# picsil_Carrier.net
KiCad netlist of a schematic drawn in EAGLE
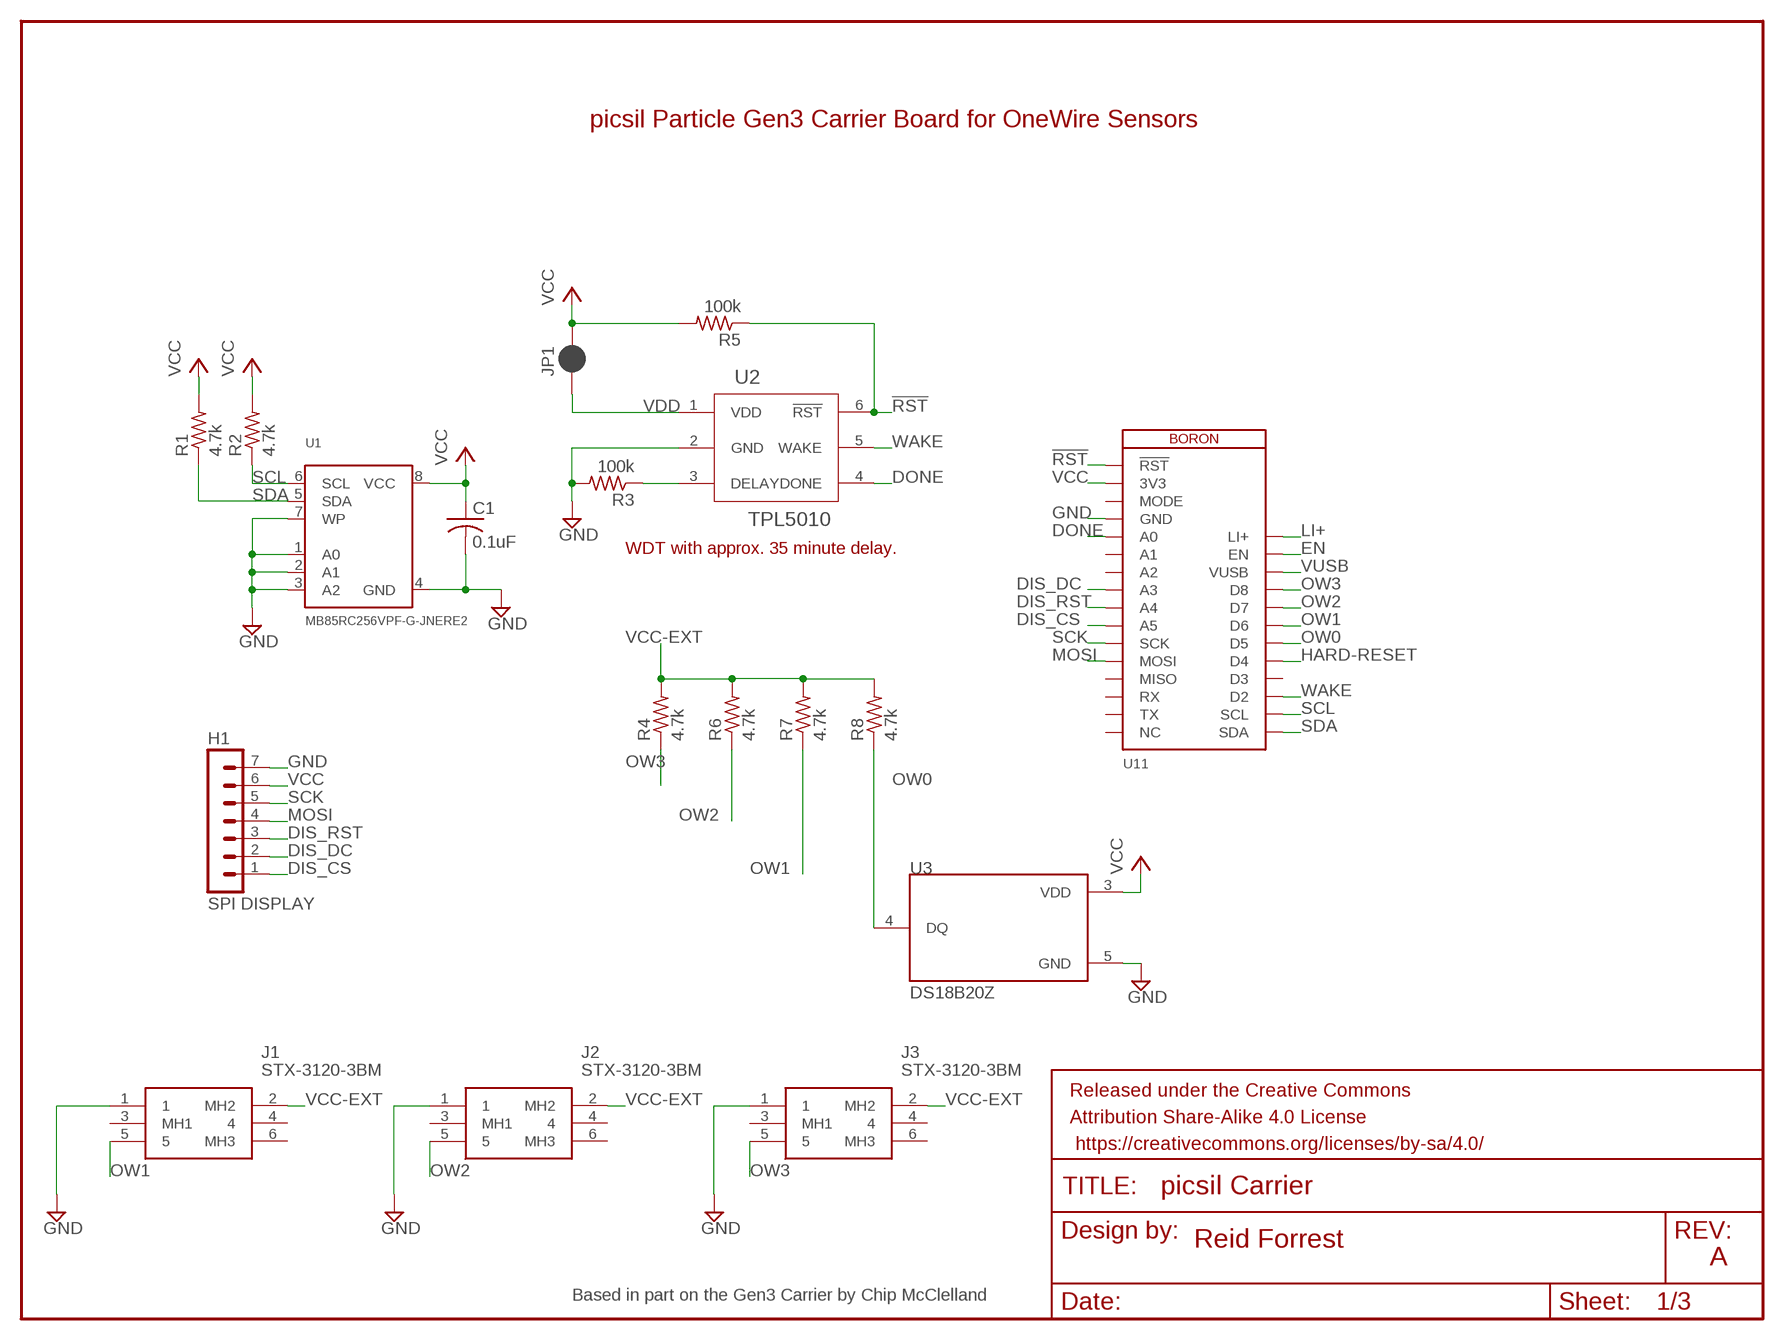
[diagram p0: schematic, sheet 1]
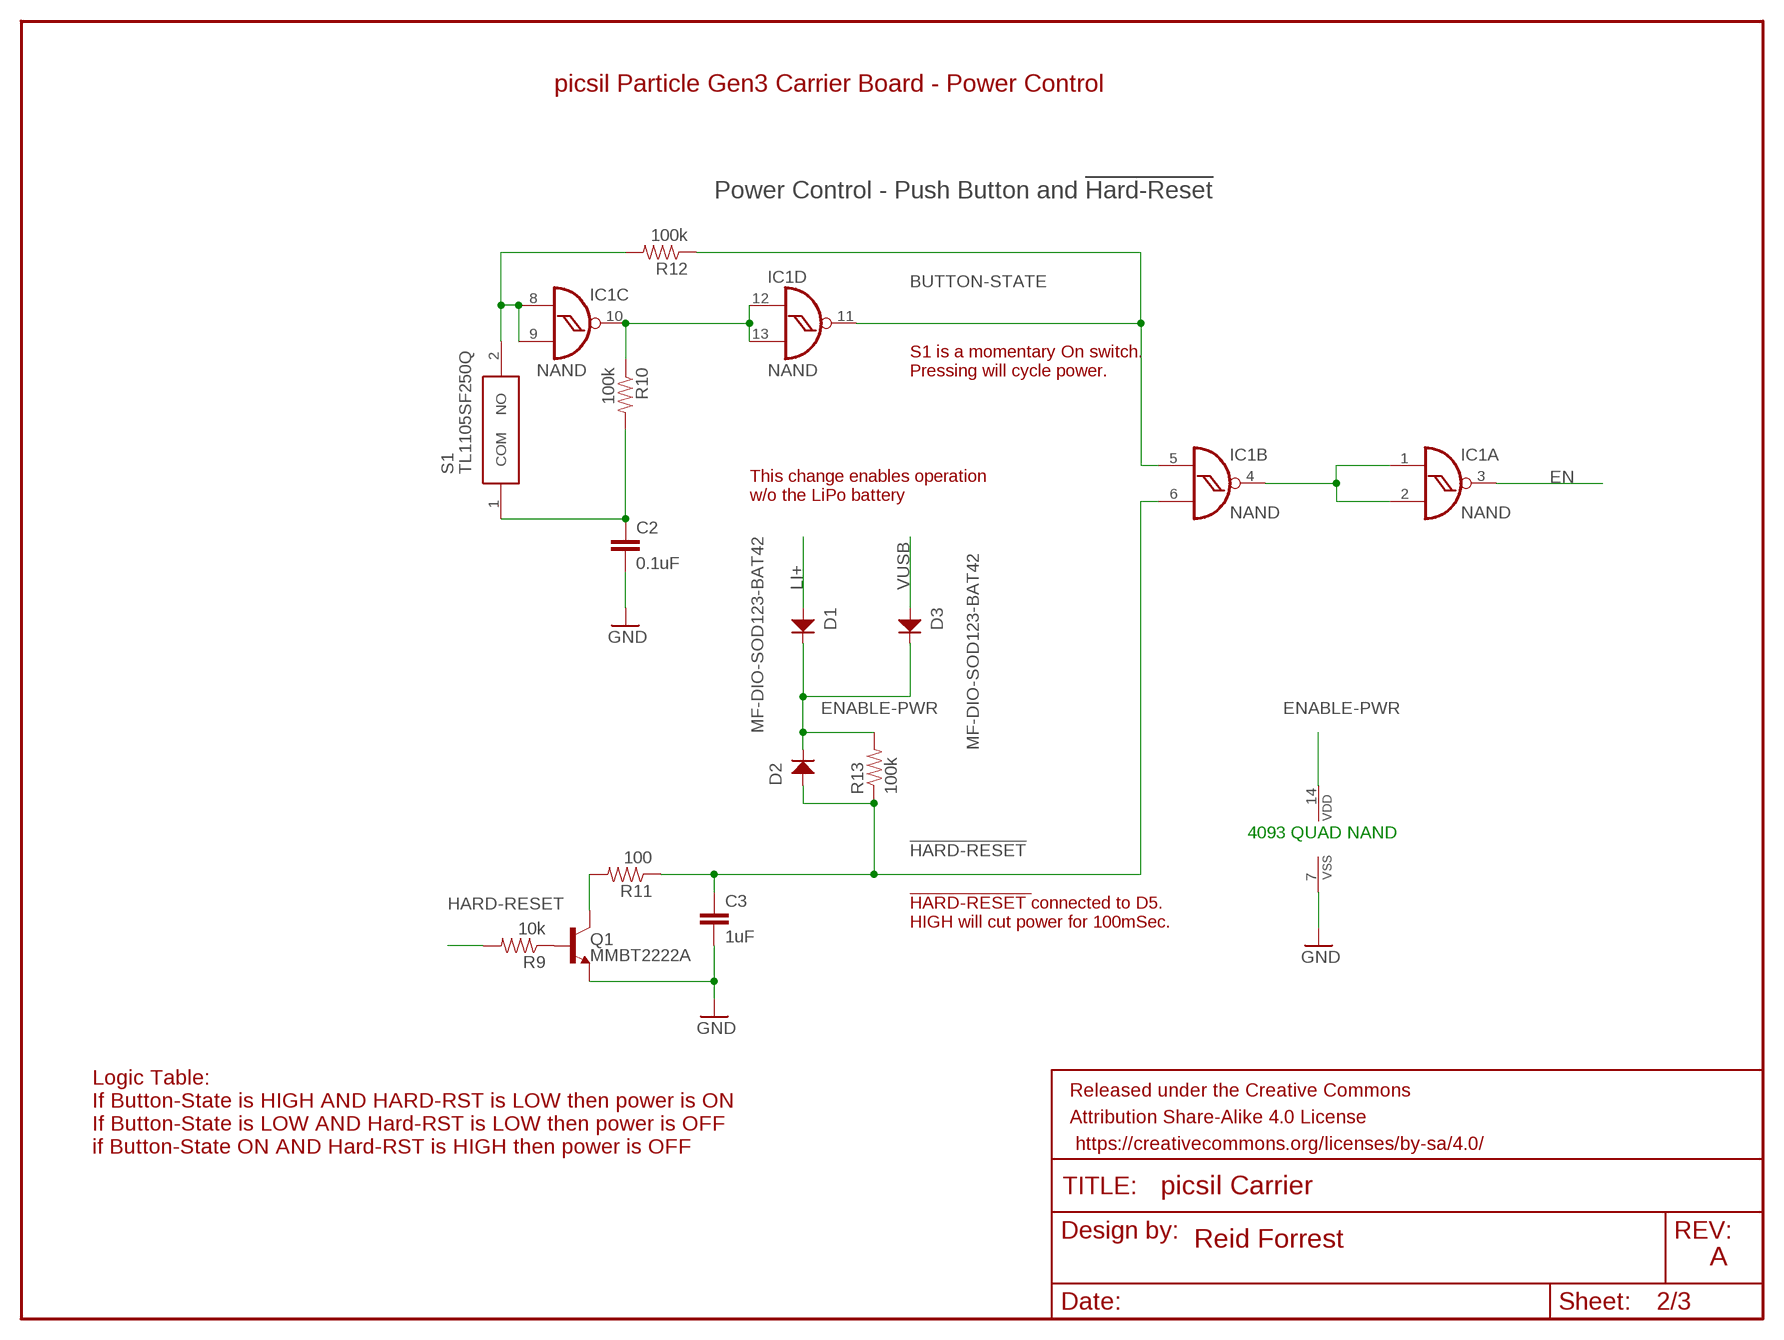
[diagram p1: schematic, sheet 2]
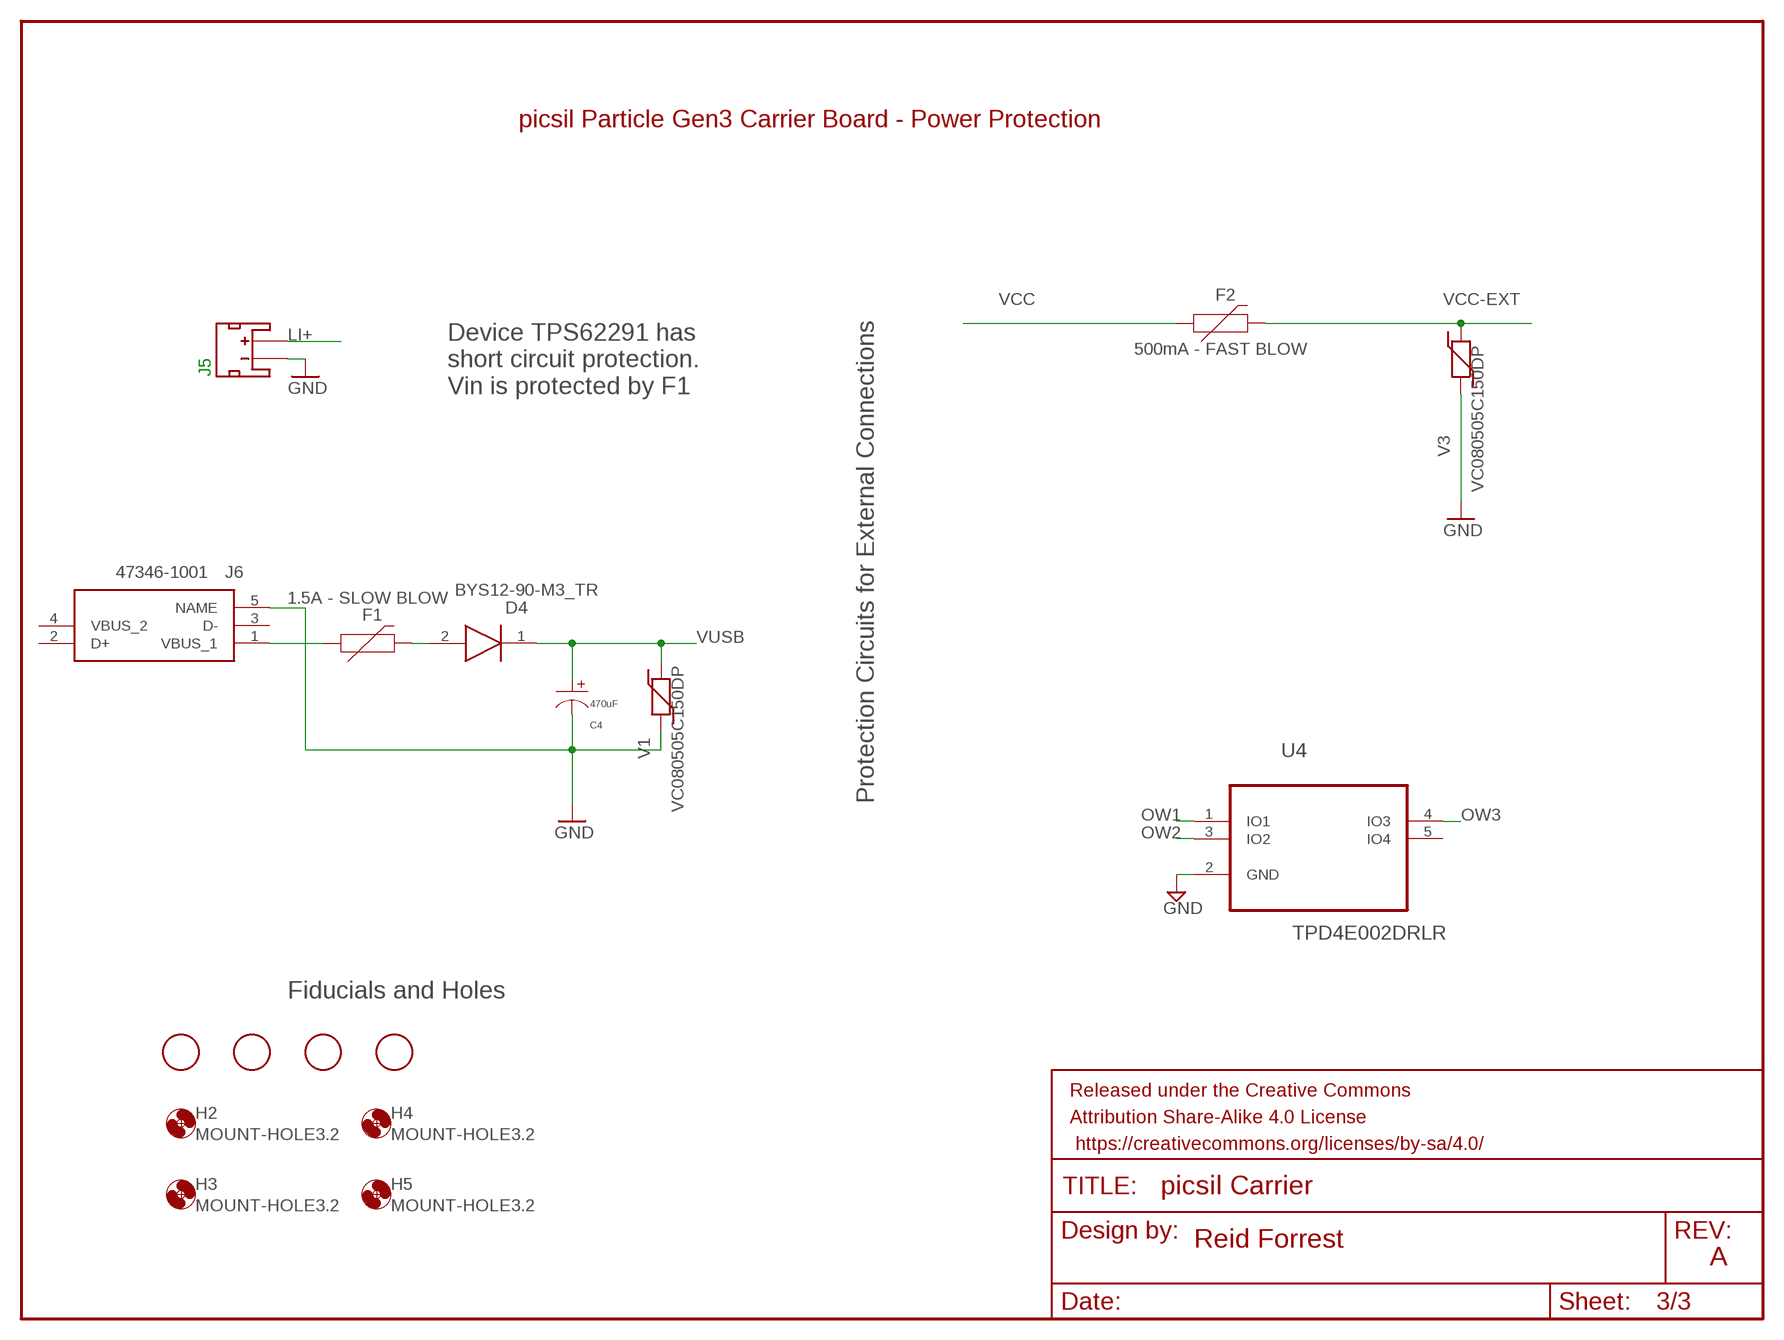
[diagram p2: schematic, sheet 3]

(export (version "E")
  (design (tool "Eeschema 10.0.6"))
  (components
    (comp (ref "C2")
      (value "0.1uF")
      (footprint "eagle-import:0805@1")
      (libsource (lib "eagle-import") (part "CAP0805"))
    )
    (comp (ref "C3")
      (value "1uF")
      (footprint "eagle-import:0805@1")
      (libsource (lib "eagle-import") (part "CAP0805"))
    )
    (comp (ref "D1")
      (value "MF-DIO-SOD123-BAT42")
      (footprint "eagle-import:SOD-123")
      (fields (field (name "HOUSEPART") "YES"))
      (libsource (lib "eagle-import") (part "DIODES_SOD-123_BAT42"))
    )
    (comp (ref "D2")
      (value "MF-DIO-SOD123-BAT42")
      (footprint "eagle-import:SOD-123")
      (fields (field (name "HOUSEPART") "YES"))
      (libsource (lib "eagle-import") (part "DIODES_SOD-123_BAT42"))
    )
    (comp (ref "D3")
      (value "MF-DIO-SOD123-BAT42")
      (footprint "eagle-import:SOD-123")
      (fields (field (name "HOUSEPART") "YES"))
      (libsource (lib "eagle-import") (part "DIODES_SOD-123_BAT42"))
    )
    (comp (ref "FRAME2")
      (value "FRAME-LETTER")
      (footprint "eagle-import:CREATIVE_COMMONS")
      (libsource (lib "eagle-import") (part "FRAME-LETTER"))
    )
    (comp (ref "IC1")
      (value "NAND")
      (footprint "eagle-import:MC14093B-TSSOP14")
      (libsource (lib "eagle-import") (part "4093DT"))
    )
    (comp (ref "Q1")
      (value "MMBT2222A")
      (footprint "eagle-import:SOT23-3")
      (libsource (lib "eagle-import") (part "TRANS_NPN-MMBT2222AL"))
    )
    (comp (ref "R9")
      (value "10k")
      (footprint "eagle-import:0805")
      (libsource (lib "eagle-import") (part "RESISTOR0805-RES"))
    )
    (comp (ref "R10")
      (value "100k")
      (footprint "eagle-import:0805")
      (libsource (lib "eagle-import") (part "RESISTOR0805-RES"))
    )
    (comp (ref "R11")
      (value "100")
      (footprint "eagle-import:0805")
      (libsource (lib "eagle-import") (part "RESISTOR0805-RES"))
    )
    (comp (ref "R12")
      (value "100k")
      (footprint "eagle-import:0805")
      (libsource (lib "eagle-import") (part "RESISTOR0805-RES"))
    )
    (comp (ref "R13")
      (value "100k")
      (footprint "eagle-import:0805")
      (libsource (lib "eagle-import") (part "RESISTOR0805-RES"))
    )
    (comp (ref "S1")
      (value "TL1105SF250Q")
      (footprint "eagle-import:TL1105SF250Q")
      (fields (field (name "MOUSER_PART_NUMBER") "612-TL1105S-250"))
      (libsource (lib "eagle-import") (part "TL1105SF250Q"))
    )
    (comp (ref "C1")
      (value "0.1uF")
      (footprint "eagle-import:C0805")
      (libsource (lib "eagle-import") (part "C-USC0805"))
    )
    (comp (ref "FRAME1")
      (value "FRAME-LETTER")
      (footprint "eagle-import:CREATIVE_COMMONS")
      (libsource (lib "eagle-import") (part "FRAME-LETTER"))
    )
    (comp (ref "FRAME4")
      (value "FRAME-LETTER")
      (footprint "eagle-import:CREATIVE_COMMONS")
      (libsource (lib "eagle-import") (part "FRAME-LETTER"))
    )
    (comp (ref "H1")
      (value "SPI DISPLAY")
      (footprint "eagle-import:MA07-1")
      (libsource (lib "eagle-import") (part "MA07-1"))
    )
    (comp (ref "J1")
      (value "STX-3120-3BM")
      (footprint "eagle-import:STX31203BM")
      (fields (field (name "MOUSER_PART_NUMBER") "806-STX-3120-3BM"))
      (libsource (lib "eagle-import") (part "STX-3120-3BM"))
    )
    (comp (ref "J2")
      (value "STX-3120-3BM")
      (footprint "eagle-import:STX31203BM")
      (fields (field (name "MOUSER_PART_NUMBER") "806-STX-3120-3BM"))
      (libsource (lib "eagle-import") (part "STX-3120-3BM"))
    )
    (comp (ref "J3")
      (value "STX-3120-3BM")
      (footprint "eagle-import:STX31203BM")
      (fields (field (name "MOUSER_PART_NUMBER") "806-STX-3120-3BM"))
      (libsource (lib "eagle-import") (part "STX-3120-3BM"))
    )
    (comp (ref "JP1")
      (value "JUMPER-SMT_2_NC_PASTE_SILK")
      (footprint "eagle-import:SMT-JUMPER_2_NC_PASTE_SILK")
      (libsource (lib "eagle-import") (part "JUMPER-SMT_2_NC_PASTE_SILK"))
    )
    (comp (ref "R1")
      (value "4.7k")
      (footprint "eagle-import:R0805")
      (libsource (lib "eagle-import") (part "R-US_R0805"))
    )
    (comp (ref "R2")
      (value "4.7k")
      (footprint "eagle-import:R0805")
      (libsource (lib "eagle-import") (part "R-US_R0805"))
    )
    (comp (ref "R3")
      (value "100k")
      (footprint "eagle-import:R0805")
      (libsource (lib "eagle-import") (part "R-US_R0805"))
    )
    (comp (ref "R4")
      (value "4.7k")
      (footprint "eagle-import:R0805")
      (libsource (lib "eagle-import") (part "R-US_R0805"))
    )
    (comp (ref "R5")
      (value "100k")
      (footprint "eagle-import:R0805")
      (libsource (lib "eagle-import") (part "R-US_R0805"))
    )
    (comp (ref "R6")
      (value "4.7k")
      (footprint "eagle-import:R0805")
      (libsource (lib "eagle-import") (part "R-US_R0805"))
    )
    (comp (ref "R7")
      (value "4.7k")
      (footprint "eagle-import:R0805")
      (libsource (lib "eagle-import") (part "R-US_R0805"))
    )
    (comp (ref "R8")
      (value "4.7k")
      (footprint "eagle-import:R0805")
      (libsource (lib "eagle-import") (part "R-US_R0805"))
    )
    (comp (ref "U1")
      (value "MB85RC256VPF-G-JNERE2")
      (footprint "eagle-import:SOIC8_208MIL")
      (libsource (lib "eagle-import") (part "FRAM_SOIC8_I2C"))
    )
    (comp (ref "U2")
      (value "TPL5010")
      (footprint "eagle-import:TSOT-23")
      (libsource (lib "eagle-import") (part "TPL5010"))
    )
    (comp (ref "U3")
      (value "DS18B20Z")
      (footprint "eagle-import:SOIC127P600X175-8N")
      (fields (field (name "MF") "Maxim Integrated") (field (name "MP") "DS18B20Z+"))
      (libsource (lib "eagle-import") (part "DS18B20Z"))
    )
    (comp (ref "U11")
      (value "BORON")
      (footprint "eagle-import:BORON")
      (libsource (lib "eagle-import") (part "BORON"))
    )
    (comp (ref "C4")
      (value "470uF")
      (footprint "eagle-import:CP10MM")
      (libsource (lib "eagle-import") (part "CAPACITOR_P_10MM"))
    )
    (comp (ref "D4")
      (value "BYS12-90-M3_TR")
      (footprint "eagle-import:DIOM5127X229N")
      (fields
        (field (name "MANUFACTURER_PART_NUMBER") "BYS12-90-M3/TR")
        (field (name "MOUSER_PART_NUMBER") "78-BYS12-90-M3TR")
      )
      (libsource (lib "eagle-import") (part "BYS12-90-M3_TR"))
    )
    (comp (ref "F1")
      (value "1.5A - SLOW BLOW")
      (footprint "eagle-import:1206")
      (libsource (lib "eagle-import") (part "PPTC_HALF-AMP"))
    )
    (comp (ref "F2")
      (value "500mA - FAST BLOW")
      (footprint "eagle-import:1206")
      (libsource (lib "eagle-import") (part "PPTC_HALF-AMP"))
    )
    (comp (ref "FRAME3")
      (value "FRAME-LETTER")
      (footprint "eagle-import:CREATIVE_COMMONS")
      (libsource (lib "eagle-import") (part "FRAME-LETTER"))
    )
    (comp (ref "H2")
      (value "MOUNT-HOLE3.2")
      (footprint "eagle-import:3,2")
      (libsource (lib "eagle-import") (part "MOUNT-HOLE3.2"))
    )
    (comp (ref "H3")
      (value "MOUNT-HOLE3.2")
      (footprint "eagle-import:3,2")
      (libsource (lib "eagle-import") (part "MOUNT-HOLE3.2"))
    )
    (comp (ref "H4")
      (value "MOUNT-HOLE3.2")
      (footprint "eagle-import:3,2")
      (libsource (lib "eagle-import") (part "MOUNT-HOLE3.2"))
    )
    (comp (ref "H5")
      (value "MOUNT-HOLE3.2")
      (footprint "eagle-import:3,2")
      (libsource (lib "eagle-import") (part "MOUNT-HOLE3.2"))
    )
    (comp (ref "J5")
      (value "S2B-PH-SM4-TB(LF)(SN)")
      (footprint "eagle-import:JST-2-SMD")
      (libsource (lib "eagle-import") (part "JST_2MM_MALE"))
    )
    (comp (ref "J6")
      (value "47346-1001")
      (footprint "eagle-import:47346-0001")
      (fields (field (name "MOUSER_PART_NUMBER") "538-47346-1001") (field (name "RS_PART_NUMBER") "1788764"))
      (libsource (lib "eagle-import") (part "47346-1001"))
    )
    (comp (ref "U$1")
      (value "FIDUCIAL")
      (footprint "eagle-import:FIDUCIAL_1MM")
      (libsource (lib "eagle-import") (part "FIDUCIAL"))
    )
    (comp (ref "U$2")
      (value "FIDUCIAL")
      (footprint "eagle-import:FIDUCIAL_1MM")
      (libsource (lib "eagle-import") (part "FIDUCIAL"))
    )
    (comp (ref "U$3")
      (value "FIDUCIAL")
      (footprint "eagle-import:FIDUCIAL_1MM")
      (libsource (lib "eagle-import") (part "FIDUCIAL"))
    )
    (comp (ref "U$4")
      (value "FIDUCIAL")
      (footprint "eagle-import:FIDUCIAL_1MM")
      (libsource (lib "eagle-import") (part "FIDUCIAL"))
    )
    (comp (ref "U4")
      (value "TPD4E002DRLR")
      (footprint "eagle-import:SOT50P280X60-5N")
      (fields (field (name "MF") "Texas Instruments"))
      (libsource (lib "eagle-import") (part "TPD4E002DRLR"))
    )
    (comp (ref "V1")
      (value "VC080505C150DP")
      (footprint "eagle-import:0805")
      (libsource (lib "eagle-import") (part "VARISTOR"))
    )
    (comp (ref "V3")
      (value "VC080505C150DP")
      (footprint "eagle-import:0805")
      (libsource (lib "eagle-import") (part "VARISTOR"))
    )
  )
  (nets
    (net (code "1") (name "BUTTON-STATE") (class "Default")
      (node (ref "IC1") (pin "11") (pinfunction "O_11") (pintype "output"))
      (node (ref "IC1") (pin "5") (pinfunction "I0_5") (pintype "input"))
      (node (ref "R12") (pin "1") (pinfunction "1_1") (pintype "passive"))
    )
    (net (code "2") (name "DIS_CS") (class "Default")
      (node (ref "H1") (pin "1") (pinfunction "1_1") (pintype "passive"))
      (node (ref "U11") (pin "10") (pinfunction "A5_10") (pintype "bidirectional"))
    )
    (net (code "3") (name "DIS_DC") (class "Default")
      (node (ref "H1") (pin "2") (pinfunction "2_2") (pintype "passive"))
      (node (ref "U11") (pin "8") (pinfunction "A3_8") (pintype "bidirectional"))
    )
    (net (code "4") (name "DIS_RST") (class "Default")
      (node (ref "H1") (pin "3") (pinfunction "3_3") (pintype "passive"))
      (node (ref "U11") (pin "9") (pinfunction "A4_9") (pintype "bidirectional"))
    )
    (net (code "5") (name "DONE") (class "Default")
      (node (ref "U11") (pin "5") (pinfunction "A0_5") (pintype "bidirectional"))
      (node (ref "U2") (pin "4") (pinfunction "DONE_4") (pintype "input"))
    )
    (net (code "6") (name "EN") (class "Default")
      (node (ref "IC1") (pin "3") (pinfunction "O_3") (pintype "output"))
      (node (ref "U11") (pin "27") (pinfunction "EN_27") (pintype "input"))
    )
    (net (code "7") (name "ENABLE-PWR") (class "Default")
      (node (ref "D1") (pin "CATHODE") (pinfunction "CATHODE_CATHODE") (pintype "bidirectional"))
      (node (ref "D2") (pin "CATHODE") (pinfunction "CATHODE_CATHODE") (pintype "bidirectional"))
      (node (ref "D3") (pin "CATHODE") (pinfunction "CATHODE_CATHODE") (pintype "bidirectional"))
      (node (ref "IC1") (pin "14") (pinfunction "VDD_14") (pintype "power_in"))
      (node (ref "R13") (pin "2") (pinfunction "2_2") (pintype "passive"))
    )
    (net (code "8") (name "GND") (class "Default")
      (node (ref "C1") (pin "2") (pinfunction "2_2") (pintype "passive"))
      (node (ref "C2") (pin "2") (pinfunction "2_2") (pintype "passive"))
      (node (ref "C3") (pin "2") (pinfunction "2_2") (pintype "passive"))
      (node (ref "C4") (pin "P$2") (pinfunction "P$2_P$2") (pintype "passive"))
      (node (ref "H1") (pin "7") (pinfunction "7_7") (pintype "passive"))
      (node (ref "IC1") (pin "7") (pinfunction "VSS_7") (pintype "power_in"))
      (node (ref "J1") (pin "1") (pinfunction "1_1") (pintype "bidirectional"))
      (node (ref "J2") (pin "1") (pinfunction "1_1") (pintype "bidirectional"))
      (node (ref "J3") (pin "1") (pinfunction "1_1") (pintype "bidirectional"))
      (node (ref "J5") (pin "1") (pinfunction "-_1") (pintype "bidirectional"))
      (node (ref "J6") (pin "5") (pinfunction "NAME_5") (pintype "bidirectional"))
      (node (ref "Q1") (pin "2") (pinfunction "E_2") (pintype "passive"))
      (node (ref "R3") (pin "2") (pinfunction "2_2") (pintype "passive"))
      (node (ref "U1") (pin "1") (pinfunction "A0_1") (pintype "input"))
      (node (ref "U1") (pin "2") (pinfunction "A1_2") (pintype "input"))
      (node (ref "U1") (pin "3") (pinfunction "A2_3") (pintype "input"))
      (node (ref "U1") (pin "4") (pinfunction "GND_4") (pintype "power_in"))
      (node (ref "U1") (pin "7") (pinfunction "WP_7") (pintype "input"))
      (node (ref "U11") (pin "4") (pinfunction "GND_4") (pintype "power_in"))
      (node (ref "U2") (pin "2") (pinfunction "GND_2") (pintype "power_in"))
      (node (ref "U3") (pin "5") (pinfunction "GND_5") (pintype "power_in"))
      (node (ref "U4") (pin "2") (pinfunction "GND_2") (pintype "passive"))
      (node (ref "V1") (pin "1") (pinfunction "1_1") (pintype "passive"))
      (node (ref "V3") (pin "1") (pinfunction "1_1") (pintype "passive"))
    )
    (net (code "9") (name "HARD-RESET") (class "Default")
      (node (ref "R9") (pin "2") (pinfunction "2_2") (pintype "passive"))
      (node (ref "U11") (pin "21") (pinfunction "D4_21") (pintype "bidirectional"))
    )
    (net (code "10") (name "LI+") (class "Default")
      (node (ref "D1") (pin "ANODE") (pinfunction "ANODE_ANODE") (pintype "bidirectional"))
      (node (ref "J5") (pin "2") (pinfunction "+_2") (pintype "bidirectional"))
      (node (ref "U11") (pin "28") (pinfunction "LI+_28") (pintype "power_in"))
    )
    (net (code "11") (name "MOSI") (class "Default")
      (node (ref "H1") (pin "4") (pinfunction "4_4") (pintype "passive"))
      (node (ref "U11") (pin "12") (pinfunction "MOSI_12") (pintype "bidirectional"))
    )
    (net (code "12") (name "Net-(D4-A)") (class "Default")
      (node (ref "D4") (pin "2") (pinfunction "A_2") (pintype "bidirectional"))
      (node (ref "F1") (pin "2") (pinfunction "2_2") (pintype "bidirectional"))
    )
    (net (code "13") (name "Net-(IC1A-I0)") (class "Default")
      (node (ref "IC1") (pin "1") (pinfunction "I0_1") (pintype "input"))
      (node (ref "IC1") (pin "2") (pinfunction "I1_2") (pintype "input"))
      (node (ref "IC1") (pin "4") (pinfunction "O_4") (pintype "output"))
    )
    (net (code "14") (name "Net-(IC1C-I0)") (class "Default")
      (node (ref "IC1") (pin "8") (pinfunction "I0_8") (pintype "input"))
      (node (ref "IC1") (pin "9") (pinfunction "I1_9") (pintype "input"))
      (node (ref "R12") (pin "2") (pinfunction "2_2") (pintype "passive"))
      (node (ref "S1") (pin "2") (pinfunction "NO_2") (pintype "bidirectional"))
    )
    (net (code "15") (name "Net-(IC1C-O)") (class "Default")
      (node (ref "IC1") (pin "10") (pinfunction "O_10") (pintype "output"))
      (node (ref "IC1") (pin "12") (pinfunction "I0_12") (pintype "input"))
      (node (ref "IC1") (pin "13") (pinfunction "I1_13") (pintype "input"))
      (node (ref "R10") (pin "1") (pinfunction "1_1") (pintype "passive"))
    )
    (net (code "16") (name "Net-(J6-VBUS_1)") (class "Default")
      (node (ref "F1") (pin "1") (pinfunction "1_1") (pintype "bidirectional"))
      (node (ref "J6") (pin "1") (pinfunction "VBUS_1_1") (pintype "bidirectional"))
    )
    (net (code "17") (name "Net-(Q1-B)") (class "Default")
      (node (ref "Q1") (pin "1") (pinfunction "B_1") (pintype "passive"))
      (node (ref "R9") (pin "1") (pinfunction "1_1") (pintype "passive"))
    )
    (net (code "18") (name "Net-(Q1-C)") (class "Default")
      (node (ref "Q1") (pin "3") (pinfunction "C_3") (pintype "passive"))
      (node (ref "R11") (pin "2") (pinfunction "2_2") (pintype "passive"))
    )
    (net (code "19") (name "Net-(S1-COM)") (class "Default")
      (node (ref "C2") (pin "1") (pinfunction "1_1") (pintype "passive"))
      (node (ref "R10") (pin "2") (pinfunction "2_2") (pintype "passive"))
      (node (ref "S1") (pin "1") (pinfunction "COM_1") (pintype "bidirectional"))
    )
    (net (code "20") (name "Net-(U2-DELAY)") (class "Default")
      (node (ref "R3") (pin "1") (pinfunction "1_1") (pintype "passive"))
      (node (ref "U2") (pin "3") (pinfunction "DELAY_3") (pintype "input"))
    )
    (net (code "21") (name "OW0") (class "Default")
      (node (ref "R8") (pin "1") (pinfunction "1_1") (pintype "passive"))
      (node (ref "U11") (pin "22") (pinfunction "D5_22") (pintype "bidirectional"))
      (node (ref "U3") (pin "4") (pinfunction "DQ_4") (pintype "bidirectional"))
    )
    (net (code "22") (name "OW1") (class "Default")
      (node (ref "J1") (pin "5") (pinfunction "5_5") (pintype "bidirectional"))
      (node (ref "R7") (pin "1") (pinfunction "1_1") (pintype "passive"))
      (node (ref "U11") (pin "23") (pinfunction "D6_23") (pintype "bidirectional"))
      (node (ref "U4") (pin "1") (pinfunction "IO1_1") (pintype "bidirectional"))
    )
    (net (code "23") (name "OW2") (class "Default")
      (node (ref "J2") (pin "5") (pinfunction "5_5") (pintype "bidirectional"))
      (node (ref "R6") (pin "1") (pinfunction "1_1") (pintype "passive"))
      (node (ref "U11") (pin "24") (pinfunction "D7_24") (pintype "bidirectional"))
      (node (ref "U4") (pin "3") (pinfunction "IO2_3") (pintype "bidirectional"))
    )
    (net (code "24") (name "OW3") (class "Default")
      (node (ref "J3") (pin "5") (pinfunction "5_5") (pintype "bidirectional"))
      (node (ref "R4") (pin "1") (pinfunction "1_1") (pintype "passive"))
      (node (ref "U11") (pin "25") (pinfunction "D8_25") (pintype "bidirectional"))
      (node (ref "U4") (pin "4") (pinfunction "IO3_4") (pintype "bidirectional"))
    )
    (net (code "25") (name "SCK") (class "Default")
      (node (ref "H1") (pin "5") (pinfunction "5_5") (pintype "passive"))
      (node (ref "U11") (pin "11") (pinfunction "SCK_11") (pintype "bidirectional"))
    )
    (net (code "26") (name "SCL") (class "Default")
      (node (ref "R2") (pin "1") (pinfunction "1_1") (pintype "passive"))
      (node (ref "U1") (pin "6") (pinfunction "SCL_6") (pintype "input"))
      (node (ref "U11") (pin "18") (pinfunction "SCL_18") (pintype "bidirectional"))
    )
    (net (code "27") (name "SDA") (class "Default")
      (node (ref "R1") (pin "1") (pinfunction "1_1") (pintype "passive"))
      (node (ref "U1") (pin "5") (pinfunction "SDA_5") (pintype "bidirectional"))
      (node (ref "U11") (pin "17") (pinfunction "SDA_17") (pintype "bidirectional"))
    )
    (net (code "28") (name "VCC") (class "Default")
      (node (ref "C1") (pin "1") (pinfunction "1_1") (pintype "passive"))
      (node (ref "F2") (pin "1") (pinfunction "1_1") (pintype "bidirectional"))
      (node (ref "H1") (pin "6") (pinfunction "6_6") (pintype "passive"))
      (node (ref "JP1") (pin "2") (pinfunction "2_2") (pintype "passive"))
      (node (ref "R1") (pin "2") (pinfunction "2_2") (pintype "passive"))
      (node (ref "R2") (pin "2") (pinfunction "2_2") (pintype "passive"))
      (node (ref "R5") (pin "2") (pinfunction "2_2") (pintype "passive"))
      (node (ref "U1") (pin "8") (pinfunction "VCC_8") (pintype "power_in"))
      (node (ref "U11") (pin "2") (pinfunction "3V3_2") (pintype "power_in"))
      (node (ref "U3") (pin "3") (pinfunction "VDD_3") (pintype "power_in"))
    )
    (net (code "29") (name "VCC-EXT") (class "Default")
      (node (ref "F2") (pin "2") (pinfunction "2_2") (pintype "bidirectional"))
      (node (ref "J1") (pin "2") (pinfunction "MH2_2") (pintype "bidirectional"))
      (node (ref "J2") (pin "2") (pinfunction "MH2_2") (pintype "bidirectional"))
      (node (ref "J3") (pin "2") (pinfunction "MH2_2") (pintype "bidirectional"))
      (node (ref "R4") (pin "2") (pinfunction "2_2") (pintype "passive"))
      (node (ref "R6") (pin "2") (pinfunction "2_2") (pintype "passive"))
      (node (ref "R7") (pin "2") (pinfunction "2_2") (pintype "passive"))
      (node (ref "R8") (pin "2") (pinfunction "2_2") (pintype "passive"))
      (node (ref "V3") (pin "2") (pinfunction "2_2") (pintype "passive"))
    )
    (net (code "30") (name "VDD") (class "Default")
      (node (ref "JP1") (pin "1") (pinfunction "1_1") (pintype "passive"))
      (node (ref "U2") (pin "1") (pinfunction "VDD_1") (pintype "power_in"))
    )
    (net (code "31") (name "VUSB") (class "Default")
      (node (ref "C4") (pin "P$1") (pinfunction "P$1_P$1") (pintype "passive"))
      (node (ref "D3") (pin "ANODE") (pinfunction "ANODE_ANODE") (pintype "bidirectional"))
      (node (ref "D4") (pin "1") (pinfunction "K_1") (pintype "bidirectional"))
      (node (ref "U11") (pin "26") (pinfunction "VUSB_26") (pintype "power_in"))
      (node (ref "V1") (pin "2") (pinfunction "2_2") (pintype "passive"))
    )
    (net (code "32") (name "WAKE") (class "Default")
      (node (ref "U11") (pin "19") (pinfunction "D2_19") (pintype "bidirectional"))
      (node (ref "U2") (pin "5") (pinfunction "WAKE_5") (pintype "bidirectional"))
    )
    (net (code "33") (name "unconnected-(J1-MH1-Pad3)") (class "Default")
      (node (ref "J1") (pin "3") (pinfunction "MH1_3") (pintype "bidirectional"))
    )
    (net (code "34") (name "unconnected-(J1-MH3-Pad6)") (class "Default")
      (node (ref "J1") (pin "6") (pinfunction "MH3_6") (pintype "bidirectional"))
    )
    (net (code "35") (name "unconnected-(J1-Pad4)") (class "Default")
      (node (ref "J1") (pin "4") (pinfunction "4_4") (pintype "bidirectional"))
    )
    (net (code "36") (name "unconnected-(J2-MH1-Pad3)") (class "Default")
      (node (ref "J2") (pin "3") (pinfunction "MH1_3") (pintype "bidirectional"))
    )
    (net (code "37") (name "unconnected-(J2-MH3-Pad6)") (class "Default")
      (node (ref "J2") (pin "6") (pinfunction "MH3_6") (pintype "bidirectional"))
    )
    (net (code "38") (name "unconnected-(J2-Pad4)") (class "Default")
      (node (ref "J2") (pin "4") (pinfunction "4_4") (pintype "bidirectional"))
    )
    (net (code "39") (name "unconnected-(J3-MH1-Pad3)") (class "Default")
      (node (ref "J3") (pin "3") (pinfunction "MH1_3") (pintype "bidirectional"))
    )
    (net (code "40") (name "unconnected-(J3-MH3-Pad6)") (class "Default")
      (node (ref "J3") (pin "6") (pinfunction "MH3_6") (pintype "bidirectional"))
    )
    (net (code "41") (name "unconnected-(J3-Pad4)") (class "Default")
      (node (ref "J3") (pin "4") (pinfunction "4_4") (pintype "bidirectional"))
    )
    (net (code "42") (name "unconnected-(J5-PAD1-PadNC1)") (class "Default")
      (node (ref "J5") (pin "NC1") (pinfunction "PAD1_NC1") (pintype "bidirectional"))
    )
    (net (code "43") (name "unconnected-(J5-PAD2-PadNC2)") (class "Default")
      (node (ref "J5") (pin "NC2") (pinfunction "PAD2_NC2") (pintype "bidirectional"))
    )
    (net (code "44") (name "unconnected-(J6-D+-Pad2)") (class "Default")
      (node (ref "J6") (pin "2") (pinfunction "D+_2") (pintype "bidirectional"))
    )
    (net (code "45") (name "unconnected-(J6-D--Pad3)") (class "Default")
      (node (ref "J6") (pin "3") (pinfunction "D-_3") (pintype "bidirectional"))
    )
    (net (code "46") (name "unconnected-(J6-VBUS_2-Pad4)") (class "Default")
      (node (ref "J6") (pin "4") (pinfunction "VBUS_2_4") (pintype "bidirectional"))
    )
    (net (code "47") (name "unconnected-(U4-IO4-Pad5)") (class "Default")
      (node (ref "U4") (pin "5") (pinfunction "IO4_5") (pintype "bidirectional"))
    )
    (net (code "48") (name "unconnected-(U11-A1-Pad6)") (class "Default")
      (node (ref "U11") (pin "6") (pinfunction "A1_6") (pintype "bidirectional"))
    )
    (net (code "49") (name "unconnected-(U11-A2-Pad7)") (class "Default")
      (node (ref "U11") (pin "7") (pinfunction "A2_7") (pintype "bidirectional"))
    )
    (net (code "50") (name "unconnected-(U11-D3-Pad20)") (class "Default")
      (node (ref "U11") (pin "20") (pinfunction "D3_20") (pintype "bidirectional"))
    )
    (net (code "51") (name "unconnected-(U11-MISO-Pad13)") (class "Default")
      (node (ref "U11") (pin "13") (pinfunction "MISO_13") (pintype "bidirectional"))
    )
    (net (code "52") (name "unconnected-(U11-MODE-Pad3)") (class "Default")
      (node (ref "U11") (pin "3") (pinfunction "MODE_3") (pintype "bidirectional"))
    )
    (net (code "53") (name "unconnected-(U11-NC-Pad16)") (class "Default")
      (node (ref "U11") (pin "16") (pinfunction "NC_16") (pintype "bidirectional"))
    )
    (net (code "54") (name "unconnected-(U11-RX-Pad14)") (class "Default")
      (node (ref "U11") (pin "14") (pinfunction "RX_14") (pintype "bidirectional"))
    )
    (net (code "55") (name "unconnected-(U11-TX-Pad15)") (class "Default")
      (node (ref "U11") (pin "15") (pinfunction "TX_15") (pintype "bidirectional"))
    )
    (net (code "56") (name "~{HARD-RESET}") (class "Default")
      (node (ref "C3") (pin "1") (pinfunction "1_1") (pintype "passive"))
      (node (ref "D2") (pin "ANODE") (pinfunction "ANODE_ANODE") (pintype "bidirectional"))
      (node (ref "IC1") (pin "6") (pinfunction "I1_6") (pintype "input"))
      (node (ref "R11") (pin "1") (pinfunction "1_1") (pintype "passive"))
      (node (ref "R13") (pin "1") (pinfunction "1_1") (pintype "passive"))
    )
    (net (code "57") (name "~{RST}") (class "Default")
      (node (ref "R5") (pin "1") (pinfunction "1_1") (pintype "passive"))
      (node (ref "U11") (pin "1") (pinfunction "~{RST}_1") (pintype "input"))
      (node (ref "U2") (pin "6") (pinfunction "~{RST}_6") (pintype "bidirectional"))
    )
  )
)
